# PGTN021_octasource_mkiii_controls.net
KiCad netlist of a schematic drawn in EAGLE
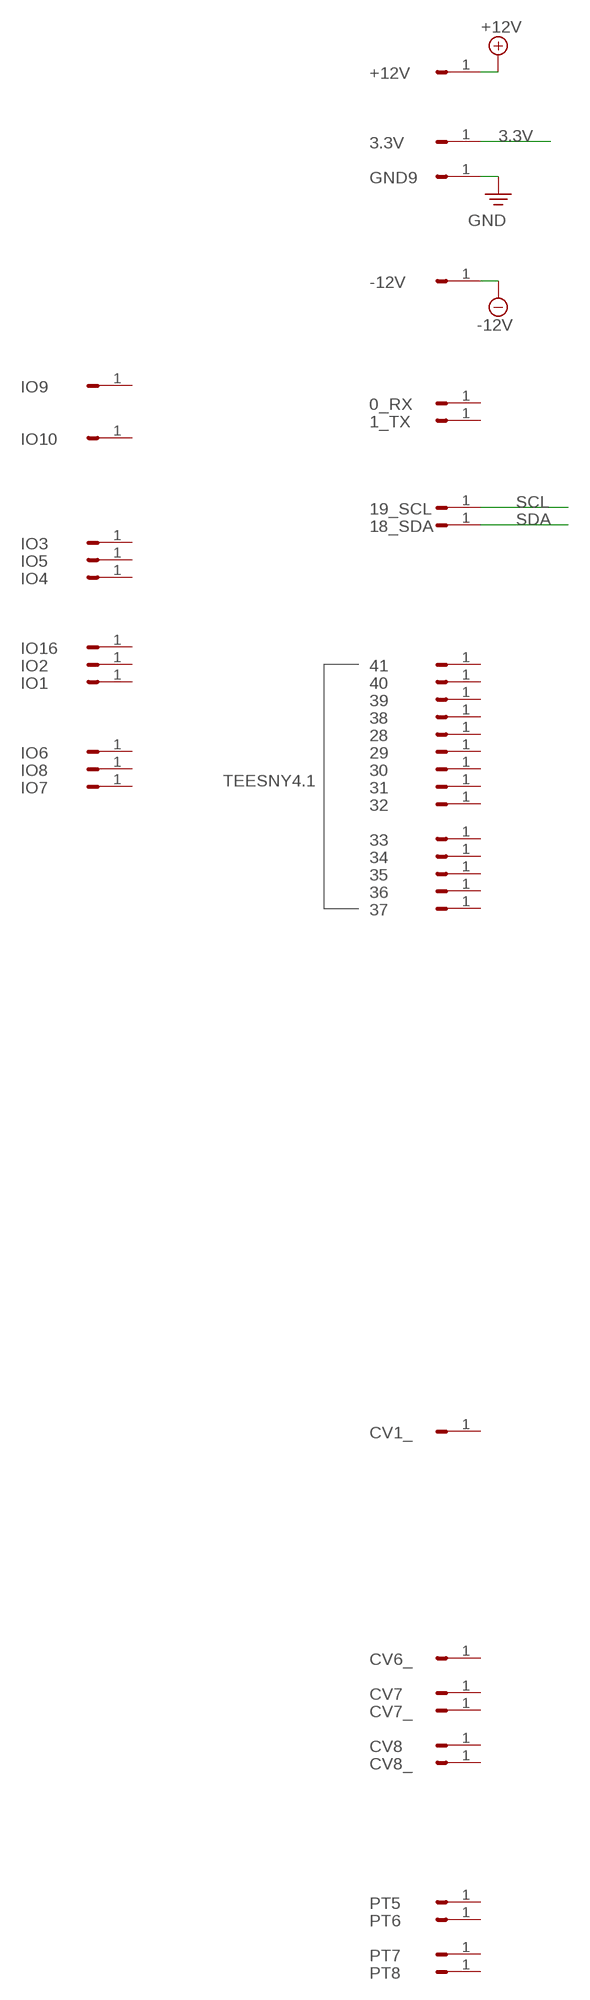
[diagram p0: schematic, sheet 1, part 1 of 2]
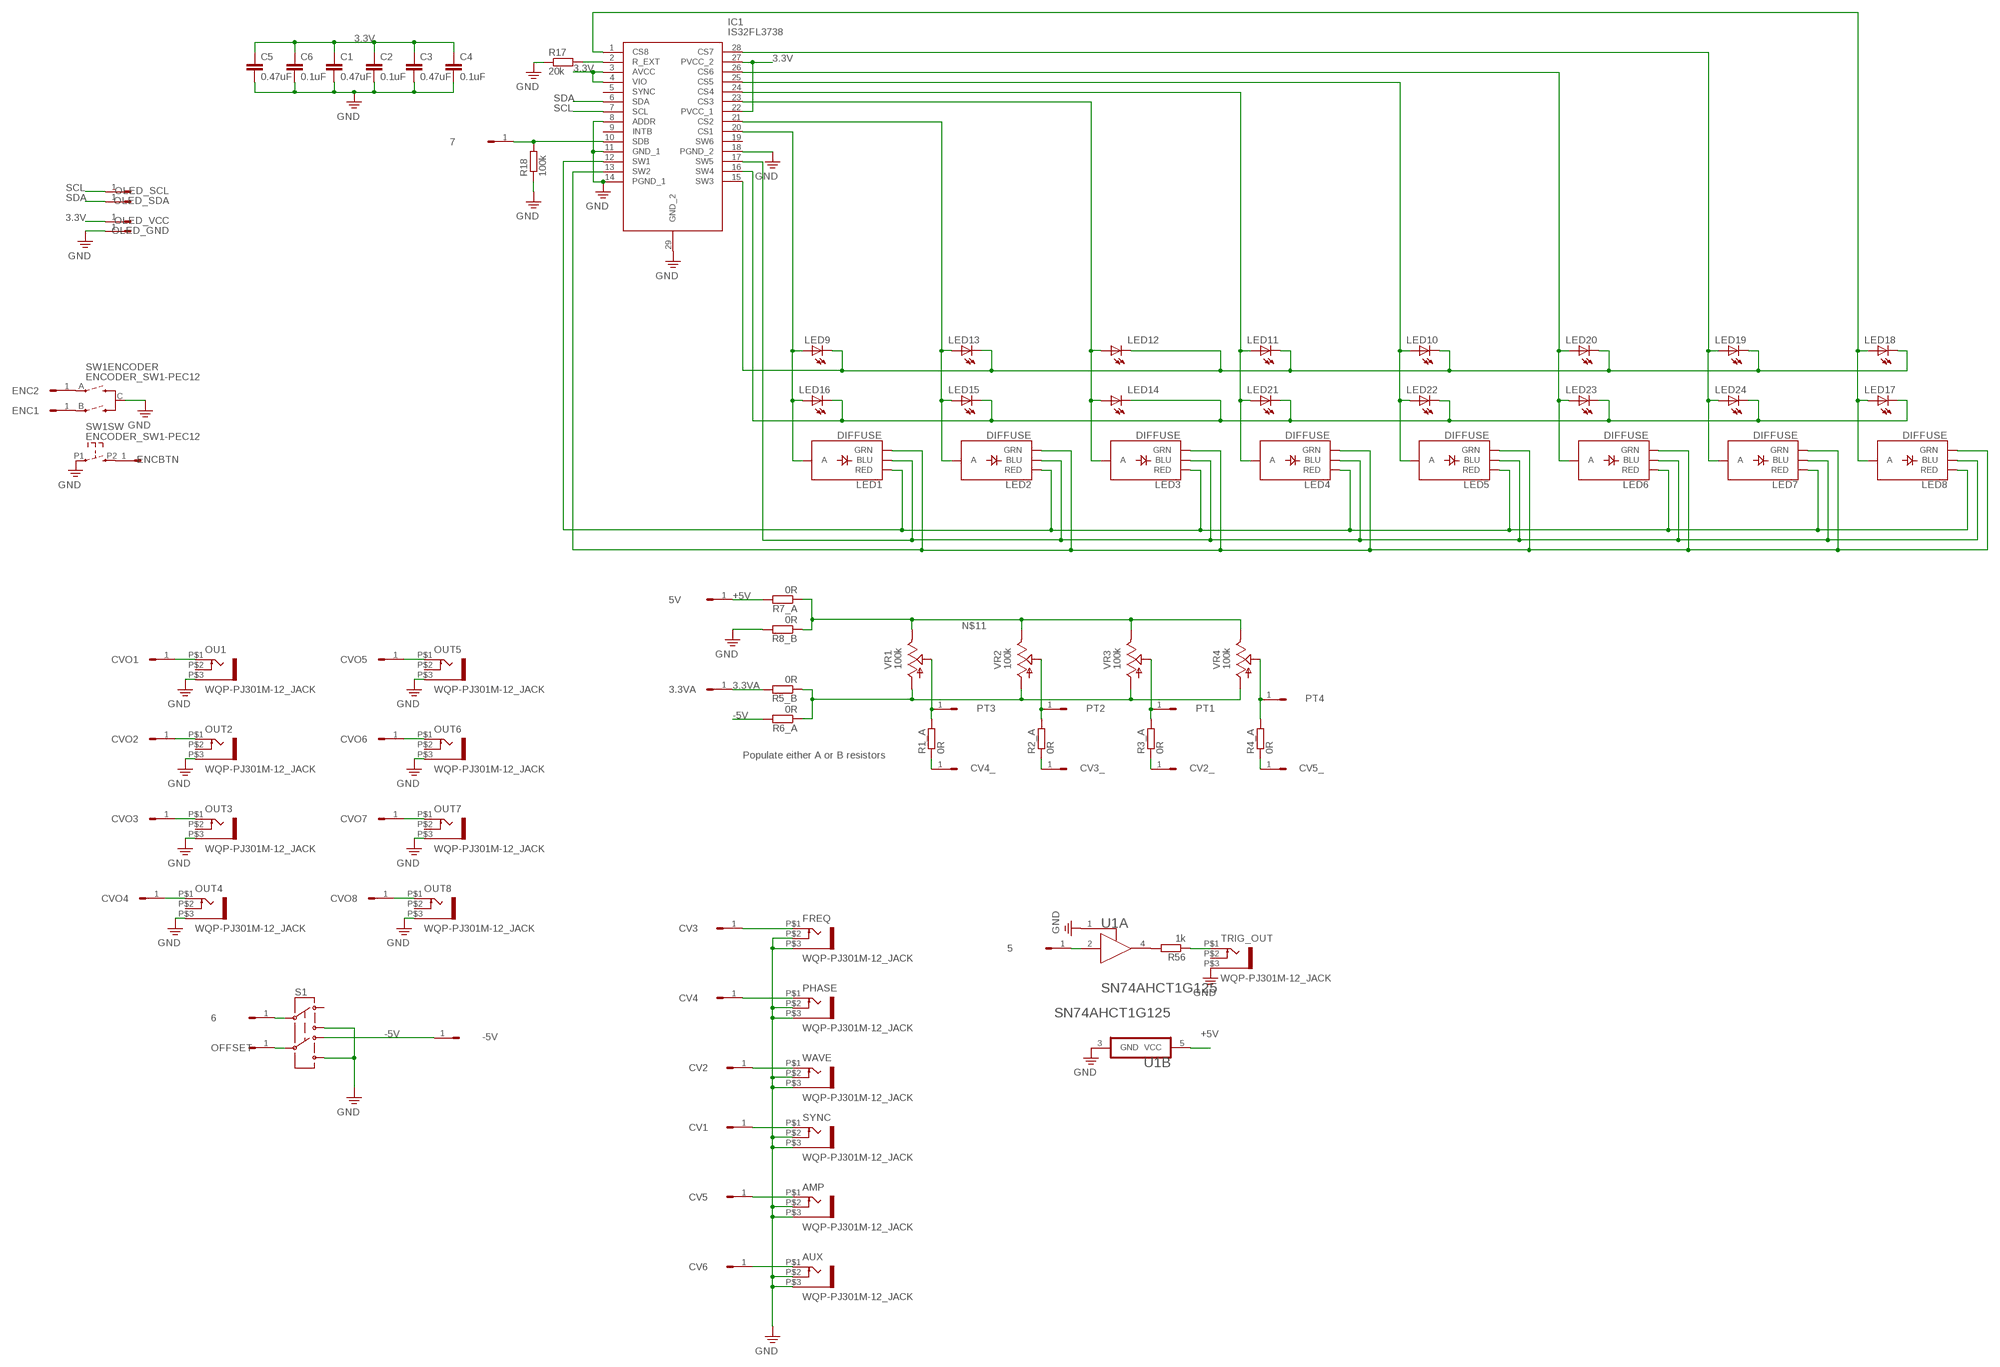
[diagram p1: schematic, sheet 1, part 2 of 2]

(export (version "E")
  (design (tool "Eeschema 10.0.6"))
  (components
    (comp (ref "+12V")
      (value "HEADER/MALE/01")
      (footprint "eagle-import:HEADER_MALE_01")
      (fields (field (name "SPICEPREFIX") "X"))
      (libsource (lib "eagle-import") (part "HEADER/MALE/01"))
    )
    (comp (ref "-5V")
      (value "HEADER/MALE/01")
      (footprint "eagle-import:HEADER_MALE_01")
      (fields (field (name "SPICEPREFIX") "X"))
      (libsource (lib "eagle-import") (part "HEADER/MALE/01"))
    )
    (comp (ref "-12V")
      (value "HEADER/MALE/01")
      (footprint "eagle-import:HEADER_MALE_01")
      (fields (field (name "SPICEPREFIX") "X"))
      (libsource (lib "eagle-import") (part "HEADER/MALE/01"))
    )
    (comp (ref "0_RX")
      (value "HEADER/MALE/01")
      (footprint "eagle-import:HEADER_MALE_01")
      (fields (field (name "SPICEPREFIX") "X"))
      (libsource (lib "eagle-import") (part "HEADER/MALE/01"))
    )
    (comp (ref "1_TX")
      (value "HEADER/MALE/01")
      (footprint "eagle-import:HEADER_MALE_01")
      (fields (field (name "SPICEPREFIX") "X"))
      (libsource (lib "eagle-import") (part "HEADER/MALE/01"))
    )
    (comp (ref "3.3V")
      (value "HEADER/MALE/01")
      (footprint "eagle-import:HEADER_MALE_01")
      (fields (field (name "SPICEPREFIX") "X"))
      (libsource (lib "eagle-import") (part "HEADER/MALE/01"))
    )
    (comp (ref "3.3VA")
      (value "HEADER/MALE/01")
      (footprint "eagle-import:HEADER_MALE_01")
      (fields (field (name "SPICEPREFIX") "X"))
      (libsource (lib "eagle-import") (part "HEADER/MALE/01"))
    )
    (comp (ref "5")
      (value "HEADER/MALE/01")
      (footprint "eagle-import:HEADER_MALE_01")
      (fields (field (name "SPICEPREFIX") "X"))
      (libsource (lib "eagle-import") (part "HEADER/MALE/01"))
    )
    (comp (ref "5V")
      (value "HEADER/MALE/01")
      (footprint "eagle-import:HEADER_MALE_01")
      (fields (field (name "SPICEPREFIX") "X"))
      (libsource (lib "eagle-import") (part "HEADER/MALE/01"))
    )
    (comp (ref "6")
      (value "HEADER/MALE/01")
      (footprint "eagle-import:HEADER_MALE_01")
      (fields (field (name "SPICEPREFIX") "X"))
      (libsource (lib "eagle-import") (part "HEADER/MALE/01"))
    )
    (comp (ref "7")
      (value "HEADER/MALE/01")
      (footprint "eagle-import:HEADER_MALE_01")
      (fields (field (name "SPICEPREFIX") "X"))
      (libsource (lib "eagle-import") (part "HEADER/MALE/01"))
    )
    (comp (ref "18_SDA")
      (value "HEADER/MALE/01")
      (footprint "eagle-import:HEADER_MALE_01")
      (fields (field (name "SPICEPREFIX") "X"))
      (libsource (lib "eagle-import") (part "HEADER/MALE/01"))
    )
    (comp (ref "19_SCL")
      (value "HEADER/MALE/01")
      (footprint "eagle-import:HEADER_MALE_01")
      (fields (field (name "SPICEPREFIX") "X"))
      (libsource (lib "eagle-import") (part "HEADER/MALE/01"))
    )
    (comp (ref "28")
      (value "HEADER/MALE/01")
      (footprint "eagle-import:HEADER_MALE_01")
      (fields (field (name "SPICEPREFIX") "X"))
      (libsource (lib "eagle-import") (part "HEADER/MALE/01"))
    )
    (comp (ref "29")
      (value "HEADER/MALE/01")
      (footprint "eagle-import:HEADER_MALE_01")
      (fields (field (name "SPICEPREFIX") "X"))
      (libsource (lib "eagle-import") (part "HEADER/MALE/01"))
    )
    (comp (ref "30")
      (value "HEADER/MALE/01")
      (footprint "eagle-import:HEADER_MALE_01")
      (fields (field (name "SPICEPREFIX") "X"))
      (libsource (lib "eagle-import") (part "HEADER/MALE/01"))
    )
    (comp (ref "31")
      (value "HEADER/MALE/01")
      (footprint "eagle-import:HEADER_MALE_01")
      (fields (field (name "SPICEPREFIX") "X"))
      (libsource (lib "eagle-import") (part "HEADER/MALE/01"))
    )
    (comp (ref "32")
      (value "HEADER/MALE/01")
      (footprint "eagle-import:HEADER_MALE_01")
      (fields (field (name "SPICEPREFIX") "X"))
      (libsource (lib "eagle-import") (part "HEADER/MALE/01"))
    )
    (comp (ref "33")
      (value "HEADER/MALE/01")
      (footprint "eagle-import:HEADER_MALE_01")
      (fields (field (name "SPICEPREFIX") "X"))
      (libsource (lib "eagle-import") (part "HEADER/MALE/01"))
    )
    (comp (ref "34")
      (value "HEADER/MALE/01")
      (footprint "eagle-import:HEADER_MALE_01")
      (fields (field (name "SPICEPREFIX") "X"))
      (libsource (lib "eagle-import") (part "HEADER/MALE/01"))
    )
    (comp (ref "35")
      (value "HEADER/MALE/01")
      (footprint "eagle-import:HEADER_MALE_01")
      (fields (field (name "SPICEPREFIX") "X"))
      (libsource (lib "eagle-import") (part "HEADER/MALE/01"))
    )
    (comp (ref "36")
      (value "HEADER/MALE/01")
      (footprint "eagle-import:HEADER_MALE_01")
      (fields (field (name "SPICEPREFIX") "X"))
      (libsource (lib "eagle-import") (part "HEADER/MALE/01"))
    )
    (comp (ref "37")
      (value "HEADER/MALE/01")
      (footprint "eagle-import:HEADER_MALE_01")
      (fields (field (name "SPICEPREFIX") "X"))
      (libsource (lib "eagle-import") (part "HEADER/MALE/01"))
    )
    (comp (ref "38")
      (value "HEADER/MALE/01")
      (footprint "eagle-import:HEADER_MALE_01")
      (fields (field (name "SPICEPREFIX") "X"))
      (libsource (lib "eagle-import") (part "HEADER/MALE/01"))
    )
    (comp (ref "39")
      (value "HEADER/MALE/01")
      (footprint "eagle-import:HEADER_MALE_01")
      (fields (field (name "SPICEPREFIX") "X"))
      (libsource (lib "eagle-import") (part "HEADER/MALE/01"))
    )
    (comp (ref "40")
      (value "HEADER/MALE/01")
      (footprint "eagle-import:HEADER_MALE_01")
      (fields (field (name "SPICEPREFIX") "X"))
      (libsource (lib "eagle-import") (part "HEADER/MALE/01"))
    )
    (comp (ref "41")
      (value "HEADER/MALE/01")
      (footprint "eagle-import:HEADER_MALE_01")
      (fields (field (name "SPICEPREFIX") "X"))
      (libsource (lib "eagle-import") (part "HEADER/MALE/01"))
    )
    (comp (ref "AMP")
      (value "WQP-PJ301M-12_JACK")
      (footprint "eagle-import:WQP-PJ301M-12_JACK")
      (libsource (lib "eagle-import") (part "WQP-PJ301M-12_JACK"))
    )
    (comp (ref "AUX")
      (value "WQP-PJ301M-12_JACK")
      (footprint "eagle-import:WQP-PJ301M-12_JACK")
      (libsource (lib "eagle-import") (part "WQP-PJ301M-12_JACK"))
    )
    (comp (ref "C1")
      (value "0.47uF")
      (footprint "eagle-import:C0603")
      (libsource (lib "eagle-import") (part "CAPACITORC0603"))
    )
    (comp (ref "C2")
      (value "0.1uF")
      (footprint "eagle-import:C0603")
      (libsource (lib "eagle-import") (part "CAPACITORC0603"))
    )
    (comp (ref "C3")
      (value "0.47uF")
      (footprint "eagle-import:C0603")
      (libsource (lib "eagle-import") (part "CAPACITORC0603"))
    )
    (comp (ref "C4")
      (value "0.1uF")
      (footprint "eagle-import:C0603")
      (libsource (lib "eagle-import") (part "CAPACITORC0603"))
    )
    (comp (ref "C5")
      (value "0.47uF")
      (footprint "eagle-import:C0603")
      (libsource (lib "eagle-import") (part "CAPACITORC0603"))
    )
    (comp (ref "C6")
      (value "0.1uF")
      (footprint "eagle-import:C0603")
      (libsource (lib "eagle-import") (part "CAPACITORC0603"))
    )
    (comp (ref "CV1")
      (value "HEADER/MALE/01")
      (footprint "eagle-import:HEADER_MALE_01")
      (fields (field (name "SPICEPREFIX") "X"))
      (libsource (lib "eagle-import") (part "HEADER/MALE/01"))
    )
    (comp (ref "CV1_")
      (value "HEADER/MALE/01")
      (footprint "eagle-import:HEADER_MALE_01")
      (fields (field (name "SPICEPREFIX") "X"))
      (libsource (lib "eagle-import") (part "HEADER/MALE/01"))
    )
    (comp (ref "CV2")
      (value "HEADER/MALE/01")
      (footprint "eagle-import:HEADER_MALE_01")
      (fields (field (name "SPICEPREFIX") "X"))
      (libsource (lib "eagle-import") (part "HEADER/MALE/01"))
    )
    (comp (ref "CV2_")
      (value "HEADER/MALE/01")
      (footprint "eagle-import:HEADER_MALE_01")
      (fields (field (name "SPICEPREFIX") "X"))
      (libsource (lib "eagle-import") (part "HEADER/MALE/01"))
    )
    (comp (ref "CV3")
      (value "HEADER/MALE/01")
      (footprint "eagle-import:HEADER_MALE_01")
      (fields (field (name "SPICEPREFIX") "X"))
      (libsource (lib "eagle-import") (part "HEADER/MALE/01"))
    )
    (comp (ref "CV3_")
      (value "HEADER/MALE/01")
      (footprint "eagle-import:HEADER_MALE_01")
      (fields (field (name "SPICEPREFIX") "X"))
      (libsource (lib "eagle-import") (part "HEADER/MALE/01"))
    )
    (comp (ref "CV4")
      (value "HEADER/MALE/01")
      (footprint "eagle-import:HEADER_MALE_01")
      (fields (field (name "SPICEPREFIX") "X"))
      (libsource (lib "eagle-import") (part "HEADER/MALE/01"))
    )
    (comp (ref "CV4_")
      (value "HEADER/MALE/01")
      (footprint "eagle-import:HEADER_MALE_01")
      (fields (field (name "SPICEPREFIX") "X"))
      (libsource (lib "eagle-import") (part "HEADER/MALE/01"))
    )
    (comp (ref "CV5")
      (value "HEADER/MALE/01")
      (footprint "eagle-import:HEADER_MALE_01")
      (fields (field (name "SPICEPREFIX") "X"))
      (libsource (lib "eagle-import") (part "HEADER/MALE/01"))
    )
    (comp (ref "CV5_")
      (value "HEADER/MALE/01")
      (footprint "eagle-import:HEADER_MALE_01")
      (fields (field (name "SPICEPREFIX") "X"))
      (libsource (lib "eagle-import") (part "HEADER/MALE/01"))
    )
    (comp (ref "CV6")
      (value "HEADER/MALE/01")
      (footprint "eagle-import:HEADER_MALE_01")
      (fields (field (name "SPICEPREFIX") "X"))
      (libsource (lib "eagle-import") (part "HEADER/MALE/01"))
    )
    (comp (ref "CV6_")
      (value "HEADER/MALE/01")
      (footprint "eagle-import:HEADER_MALE_01")
      (fields (field (name "SPICEPREFIX") "X"))
      (libsource (lib "eagle-import") (part "HEADER/MALE/01"))
    )
    (comp (ref "CV7")
      (value "HEADER/MALE/01")
      (footprint "eagle-import:HEADER_MALE_01")
      (fields (field (name "SPICEPREFIX") "X"))
      (libsource (lib "eagle-import") (part "HEADER/MALE/01"))
    )
    (comp (ref "CV7_")
      (value "HEADER/MALE/01")
      (footprint "eagle-import:HEADER_MALE_01")
      (fields (field (name "SPICEPREFIX") "X"))
      (libsource (lib "eagle-import") (part "HEADER/MALE/01"))
    )
    (comp (ref "CV8")
      (value "HEADER/MALE/01")
      (footprint "eagle-import:HEADER_MALE_01")
      (fields (field (name "SPICEPREFIX") "X"))
      (libsource (lib "eagle-import") (part "HEADER/MALE/01"))
    )
    (comp (ref "CV8_")
      (value "HEADER/MALE/01")
      (footprint "eagle-import:HEADER_MALE_01")
      (fields (field (name "SPICEPREFIX") "X"))
      (libsource (lib "eagle-import") (part "HEADER/MALE/01"))
    )
    (comp (ref "CVO1")
      (value "HEADER/MALE/01")
      (footprint "eagle-import:HEADER_MALE_01")
      (fields (field (name "SPICEPREFIX") "X"))
      (libsource (lib "eagle-import") (part "HEADER/MALE/01"))
    )
    (comp (ref "CVO2")
      (value "HEADER/MALE/01")
      (footprint "eagle-import:HEADER_MALE_01")
      (fields (field (name "SPICEPREFIX") "X"))
      (libsource (lib "eagle-import") (part "HEADER/MALE/01"))
    )
    (comp (ref "CVO3")
      (value "HEADER/MALE/01")
      (footprint "eagle-import:HEADER_MALE_01")
      (fields (field (name "SPICEPREFIX") "X"))
      (libsource (lib "eagle-import") (part "HEADER/MALE/01"))
    )
    (comp (ref "CVO4")
      (value "HEADER/MALE/01")
      (footprint "eagle-import:HEADER_MALE_01")
      (fields (field (name "SPICEPREFIX") "X"))
      (libsource (lib "eagle-import") (part "HEADER/MALE/01"))
    )
    (comp (ref "CVO5")
      (value "HEADER/MALE/01")
      (footprint "eagle-import:HEADER_MALE_01")
      (fields (field (name "SPICEPREFIX") "X"))
      (libsource (lib "eagle-import") (part "HEADER/MALE/01"))
    )
    (comp (ref "CVO6")
      (value "HEADER/MALE/01")
      (footprint "eagle-import:HEADER_MALE_01")
      (fields (field (name "SPICEPREFIX") "X"))
      (libsource (lib "eagle-import") (part "HEADER/MALE/01"))
    )
    (comp (ref "CVO7")
      (value "HEADER/MALE/01")
      (footprint "eagle-import:HEADER_MALE_01")
      (fields (field (name "SPICEPREFIX") "X"))
      (libsource (lib "eagle-import") (part "HEADER/MALE/01"))
    )
    (comp (ref "CVO8")
      (value "HEADER/MALE/01")
      (footprint "eagle-import:HEADER_MALE_01")
      (fields (field (name "SPICEPREFIX") "X"))
      (libsource (lib "eagle-import") (part "HEADER/MALE/01"))
    )
    (comp (ref "ENC1")
      (value "HEADER/MALE/01")
      (footprint "eagle-import:HEADER_MALE_01")
      (fields (field (name "SPICEPREFIX") "X"))
      (libsource (lib "eagle-import") (part "HEADER/MALE/01"))
    )
    (comp (ref "ENC2")
      (value "HEADER/MALE/01")
      (footprint "eagle-import:HEADER_MALE_01")
      (fields (field (name "SPICEPREFIX") "X"))
      (libsource (lib "eagle-import") (part "HEADER/MALE/01"))
    )
    (comp (ref "ENCBTN")
      (value "HEADER/MALE/01")
      (footprint "eagle-import:HEADER_MALE_01")
      (fields (field (name "SPICEPREFIX") "X"))
      (libsource (lib "eagle-import") (part "HEADER/MALE/01"))
    )
    (comp (ref "FREQ")
      (value "WQP-PJ301M-12_JACK")
      (footprint "eagle-import:WQP-PJ301M-12_JACK")
      (libsource (lib "eagle-import") (part "WQP-PJ301M-12_JACK"))
    )
    (comp (ref "GND9")
      (value "HEADER/MALE/01")
      (footprint "eagle-import:HEADER_MALE_01")
      (fields (field (name "SPICEPREFIX") "X"))
      (libsource (lib "eagle-import") (part "HEADER/MALE/01"))
    )
    (comp (ref "IC1")
      (value "IS32FL3738")
      (footprint "eagle-import:TSSOP29")
      (fields (field (name "MANUFACTURER_PART_NUMBER") "IS32FL3738-ZLA3-TR"))
      (libsource (lib "eagle-import") (part "IS32FL3738"))
    )
    (comp (ref "IO1")
      (value "HEADER/MALE/01")
      (footprint "eagle-import:HEADER_MALE_01")
      (fields (field (name "SPICEPREFIX") "X"))
      (libsource (lib "eagle-import") (part "HEADER/MALE/01"))
    )
    (comp (ref "IO2")
      (value "HEADER/MALE/01")
      (footprint "eagle-import:HEADER_MALE_01")
      (fields (field (name "SPICEPREFIX") "X"))
      (libsource (lib "eagle-import") (part "HEADER/MALE/01"))
    )
    (comp (ref "IO3")
      (value "HEADER/MALE/01")
      (footprint "eagle-import:HEADER_MALE_01")
      (fields (field (name "SPICEPREFIX") "X"))
      (libsource (lib "eagle-import") (part "HEADER/MALE/01"))
    )
    (comp (ref "IO4")
      (value "HEADER/MALE/01")
      (footprint "eagle-import:HEADER_MALE_01")
      (fields (field (name "SPICEPREFIX") "X"))
      (libsource (lib "eagle-import") (part "HEADER/MALE/01"))
    )
    (comp (ref "IO5")
      (value "HEADER/MALE/01")
      (footprint "eagle-import:HEADER_MALE_01")
      (fields (field (name "SPICEPREFIX") "X"))
      (libsource (lib "eagle-import") (part "HEADER/MALE/01"))
    )
    (comp (ref "IO6")
      (value "HEADER/MALE/01")
      (footprint "eagle-import:HEADER_MALE_01")
      (fields (field (name "SPICEPREFIX") "X"))
      (libsource (lib "eagle-import") (part "HEADER/MALE/01"))
    )
    (comp (ref "IO7")
      (value "HEADER/MALE/01")
      (footprint "eagle-import:HEADER_MALE_01")
      (fields (field (name "SPICEPREFIX") "X"))
      (libsource (lib "eagle-import") (part "HEADER/MALE/01"))
    )
    (comp (ref "IO8")
      (value "HEADER/MALE/01")
      (footprint "eagle-import:HEADER_MALE_01")
      (fields (field (name "SPICEPREFIX") "X"))
      (libsource (lib "eagle-import") (part "HEADER/MALE/01"))
    )
    (comp (ref "IO9")
      (value "HEADER/MALE/01")
      (footprint "eagle-import:HEADER_MALE_01")
      (fields (field (name "SPICEPREFIX") "X"))
      (libsource (lib "eagle-import") (part "HEADER/MALE/01"))
    )
    (comp (ref "IO10")
      (value "HEADER/MALE/01")
      (footprint "eagle-import:HEADER_MALE_01")
      (fields (field (name "SPICEPREFIX") "X"))
      (libsource (lib "eagle-import") (part "HEADER/MALE/01"))
    )
    (comp (ref "IO16")
      (value "HEADER/MALE/01")
      (footprint "eagle-import:HEADER_MALE_01")
      (fields (field (name "SPICEPREFIX") "X"))
      (libsource (lib "eagle-import") (part "HEADER/MALE/01"))
    )
    (comp (ref "LED1")
      (value "DIFFUSE")
      (footprint "eagle-import:LED-RGB-THRU")
      (libsource (lib "eagle-import") (part "LED-RGB-CADIFFUSE"))
    )
    (comp (ref "LED2")
      (value "DIFFUSE")
      (footprint "eagle-import:LED-RGB-THRU")
      (libsource (lib "eagle-import") (part "LED-RGB-CADIFFUSE"))
    )
    (comp (ref "LED3")
      (value "DIFFUSE")
      (footprint "eagle-import:LED-RGB-THRU")
      (libsource (lib "eagle-import") (part "LED-RGB-CADIFFUSE"))
    )
    (comp (ref "LED4")
      (value "DIFFUSE")
      (footprint "eagle-import:LED-RGB-THRU")
      (libsource (lib "eagle-import") (part "LED-RGB-CADIFFUSE"))
    )
    (comp (ref "LED5")
      (value "DIFFUSE")
      (footprint "eagle-import:LED-RGB-THRU")
      (libsource (lib "eagle-import") (part "LED-RGB-CADIFFUSE"))
    )
    (comp (ref "LED6")
      (value "DIFFUSE")
      (footprint "eagle-import:LED-RGB-THRU")
      (libsource (lib "eagle-import") (part "LED-RGB-CADIFFUSE"))
    )
    (comp (ref "LED7")
      (value "DIFFUSE")
      (footprint "eagle-import:LED-RGB-THRU")
      (libsource (lib "eagle-import") (part "LED-RGB-CADIFFUSE"))
    )
    (comp (ref "LED8")
      (value "DIFFUSE")
      (footprint "eagle-import:LED-RGB-THRU")
      (libsource (lib "eagle-import") (part "LED-RGB-CADIFFUSE"))
    )
    (comp (ref "LED9")
      (value "LEDCHIPLED_0805")
      (footprint "eagle-import:CHIPLED_0805")
      (libsource (lib "eagle-import") (part "LEDCHIPLED_0805"))
    )
    (comp (ref "LED10")
      (value "LEDCHIPLED_0805")
      (footprint "eagle-import:CHIPLED_0805")
      (libsource (lib "eagle-import") (part "LEDCHIPLED_0805"))
    )
    (comp (ref "LED11")
      (value "LEDCHIPLED_0805")
      (footprint "eagle-import:CHIPLED_0805")
      (libsource (lib "eagle-import") (part "LEDCHIPLED_0805"))
    )
    (comp (ref "LED12")
      (value "LEDCHIPLED_0805")
      (footprint "eagle-import:CHIPLED_0805")
      (libsource (lib "eagle-import") (part "LEDCHIPLED_0805"))
    )
    (comp (ref "LED13")
      (value "LEDCHIPLED_0805")
      (footprint "eagle-import:CHIPLED_0805")
      (libsource (lib "eagle-import") (part "LEDCHIPLED_0805"))
    )
    (comp (ref "LED14")
      (value "LEDCHIPLED_0805")
      (footprint "eagle-import:CHIPLED_0805")
      (libsource (lib "eagle-import") (part "LEDCHIPLED_0805"))
    )
    (comp (ref "LED15")
      (value "LEDCHIPLED_0805")
      (footprint "eagle-import:CHIPLED_0805")
      (libsource (lib "eagle-import") (part "LEDCHIPLED_0805"))
    )
    (comp (ref "LED16")
      (value "LEDCHIPLED_0805")
      (footprint "eagle-import:CHIPLED_0805")
      (libsource (lib "eagle-import") (part "LEDCHIPLED_0805"))
    )
    (comp (ref "LED17")
      (value "LEDCHIPLED_0805")
      (footprint "eagle-import:CHIPLED_0805")
      (libsource (lib "eagle-import") (part "LEDCHIPLED_0805"))
    )
    (comp (ref "LED18")
      (value "LEDCHIPLED_0805")
      (footprint "eagle-import:CHIPLED_0805")
      (libsource (lib "eagle-import") (part "LEDCHIPLED_0805"))
    )
    (comp (ref "LED19")
      (value "LEDCHIPLED_0805")
      (footprint "eagle-import:CHIPLED_0805")
      (libsource (lib "eagle-import") (part "LEDCHIPLED_0805"))
    )
    (comp (ref "LED20")
      (value "LEDCHIPLED_0805")
      (footprint "eagle-import:CHIPLED_0805")
      (libsource (lib "eagle-import") (part "LEDCHIPLED_0805"))
    )
    (comp (ref "LED21")
      (value "LEDCHIPLED_0805")
      (footprint "eagle-import:CHIPLED_0805")
      (libsource (lib "eagle-import") (part "LEDCHIPLED_0805"))
    )
    (comp (ref "LED22")
      (value "LEDCHIPLED_0805")
      (footprint "eagle-import:CHIPLED_0805")
      (libsource (lib "eagle-import") (part "LEDCHIPLED_0805"))
    )
    (comp (ref "LED23")
      (value "LEDCHIPLED_0805")
      (footprint "eagle-import:CHIPLED_0805")
      (libsource (lib "eagle-import") (part "LEDCHIPLED_0805"))
    )
    (comp (ref "LED24")
      (value "LEDCHIPLED_0805")
      (footprint "eagle-import:CHIPLED_0805")
      (libsource (lib "eagle-import") (part "LEDCHIPLED_0805"))
    )
    (comp (ref "OFFSET")
      (value "HEADER/MALE/01")
      (footprint "eagle-import:HEADER_MALE_01")
      (fields (field (name "SPICEPREFIX") "X"))
      (libsource (lib "eagle-import") (part "HEADER/MALE/01"))
    )
    (comp (ref "OLED_GND")
      (value "HEADER/MALE/01")
      (footprint "eagle-import:HEADER_MALE_01")
      (fields (field (name "SPICEPREFIX") "X"))
      (libsource (lib "eagle-import") (part "HEADER/MALE/01"))
    )
    (comp (ref "OLED_SCL")
      (value "HEADER/MALE/01")
      (footprint "eagle-import:HEADER_MALE_01")
      (fields (field (name "SPICEPREFIX") "X"))
      (libsource (lib "eagle-import") (part "HEADER/MALE/01"))
    )
    (comp (ref "OLED_SDA")
      (value "HEADER/MALE/01")
      (footprint "eagle-import:HEADER_MALE_01")
      (fields (field (name "SPICEPREFIX") "X"))
      (libsource (lib "eagle-import") (part "HEADER/MALE/01"))
    )
    (comp (ref "OLED_VCC")
      (value "HEADER/MALE/01")
      (footprint "eagle-import:HEADER_MALE_01")
      (fields (field (name "SPICEPREFIX") "X"))
      (libsource (lib "eagle-import") (part "HEADER/MALE/01"))
    )
    (comp (ref "OU1")
      (value "WQP-PJ301M-12_JACK")
      (footprint "eagle-import:WQP-PJ301M-12_JACK")
      (libsource (lib "eagle-import") (part "WQP-PJ301M-12_JACK"))
    )
    (comp (ref "OUT2")
      (value "WQP-PJ301M-12_JACK")
      (footprint "eagle-import:WQP-PJ301M-12_JACK")
      (libsource (lib "eagle-import") (part "WQP-PJ301M-12_JACK"))
    )
    (comp (ref "OUT3")
      (value "WQP-PJ301M-12_JACK")
      (footprint "eagle-import:WQP-PJ301M-12_JACK")
      (libsource (lib "eagle-import") (part "WQP-PJ301M-12_JACK"))
    )
    (comp (ref "OUT4")
      (value "WQP-PJ301M-12_JACK")
      (footprint "eagle-import:WQP-PJ301M-12_JACK")
      (libsource (lib "eagle-import") (part "WQP-PJ301M-12_JACK"))
    )
    (comp (ref "OUT5")
      (value "WQP-PJ301M-12_JACK")
      (footprint "eagle-import:WQP-PJ301M-12_JACK")
      (libsource (lib "eagle-import") (part "WQP-PJ301M-12_JACK"))
    )
    (comp (ref "OUT6")
      (value "WQP-PJ301M-12_JACK")
      (footprint "eagle-import:WQP-PJ301M-12_JACK")
      (libsource (lib "eagle-import") (part "WQP-PJ301M-12_JACK"))
    )
    (comp (ref "OUT7")
      (value "WQP-PJ301M-12_JACK")
      (footprint "eagle-import:WQP-PJ301M-12_JACK")
      (libsource (lib "eagle-import") (part "WQP-PJ301M-12_JACK"))
    )
    (comp (ref "OUT8")
      (value "WQP-PJ301M-12_JACK")
      (footprint "eagle-import:WQP-PJ301M-12_JACK")
      (libsource (lib "eagle-import") (part "WQP-PJ301M-12_JACK"))
    )
    (comp (ref "PHASE")
      (value "WQP-PJ301M-12_JACK")
      (footprint "eagle-import:WQP-PJ301M-12_JACK")
      (libsource (lib "eagle-import") (part "WQP-PJ301M-12_JACK"))
    )
    (comp (ref "PT1")
      (value "HEADER/MALE/01")
      (footprint "eagle-import:HEADER_MALE_01")
      (fields (field (name "SPICEPREFIX") "X"))
      (libsource (lib "eagle-import") (part "HEADER/MALE/01"))
    )
    (comp (ref "PT2")
      (value "HEADER/MALE/01")
      (footprint "eagle-import:HEADER_MALE_01")
      (fields (field (name "SPICEPREFIX") "X"))
      (libsource (lib "eagle-import") (part "HEADER/MALE/01"))
    )
    (comp (ref "PT3")
      (value "HEADER/MALE/01")
      (footprint "eagle-import:HEADER_MALE_01")
      (fields (field (name "SPICEPREFIX") "X"))
      (libsource (lib "eagle-import") (part "HEADER/MALE/01"))
    )
    (comp (ref "PT4")
      (value "HEADER/MALE/01")
      (footprint "eagle-import:HEADER_MALE_01")
      (fields (field (name "SPICEPREFIX") "X"))
      (libsource (lib "eagle-import") (part "HEADER/MALE/01"))
    )
    (comp (ref "PT5")
      (value "HEADER/MALE/01")
      (footprint "eagle-import:HEADER_MALE_01")
      (fields (field (name "SPICEPREFIX") "X"))
      (libsource (lib "eagle-import") (part "HEADER/MALE/01"))
    )
    (comp (ref "PT6")
      (value "HEADER/MALE/01")
      (footprint "eagle-import:HEADER_MALE_01")
      (fields (field (name "SPICEPREFIX") "X"))
      (libsource (lib "eagle-import") (part "HEADER/MALE/01"))
    )
    (comp (ref "PT7")
      (value "HEADER/MALE/01")
      (footprint "eagle-import:HEADER_MALE_01")
      (fields (field (name "SPICEPREFIX") "X"))
      (libsource (lib "eagle-import") (part "HEADER/MALE/01"))
    )
    (comp (ref "PT8")
      (value "HEADER/MALE/01")
      (footprint "eagle-import:HEADER_MALE_01")
      (fields (field (name "SPICEPREFIX") "X"))
      (libsource (lib "eagle-import") (part "HEADER/MALE/01"))
    )
    (comp (ref "R1_A")
      (value "0R")
      (footprint "eagle-import:R0603")
      (libsource (lib "eagle-import") (part "RESISTOR"))
    )
    (comp (ref "R2_A")
      (value "0R")
      (footprint "eagle-import:R0603")
      (libsource (lib "eagle-import") (part "RESISTOR"))
    )
    (comp (ref "R3_A")
      (value "0R")
      (footprint "eagle-import:R0603")
      (libsource (lib "eagle-import") (part "RESISTOR"))
    )
    (comp (ref "R4_A")
      (value "0R")
      (footprint "eagle-import:R0603")
      (libsource (lib "eagle-import") (part "RESISTOR"))
    )
    (comp (ref "R5_B")
      (value "0R")
      (footprint "eagle-import:R0603")
      (libsource (lib "eagle-import") (part "RESISTOR"))
    )
    (comp (ref "R6_A")
      (value "0R")
      (footprint "eagle-import:R0603")
      (libsource (lib "eagle-import") (part "RESISTOR"))
    )
    (comp (ref "R7_A")
      (value "0R")
      (footprint "eagle-import:R0603")
      (libsource (lib "eagle-import") (part "RESISTOR"))
    )
    (comp (ref "R8_B")
      (value "0R")
      (footprint "eagle-import:R0603")
      (libsource (lib "eagle-import") (part "RESISTOR"))
    )
    (comp (ref "R17")
      (value "20k")
      (footprint "eagle-import:R0603")
      (libsource (lib "eagle-import") (part "RESISTOR"))
    )
    (comp (ref "R18")
      (value "100k")
      (footprint "eagle-import:R0603")
      (libsource (lib "eagle-import") (part "RESISTOR"))
    )
    (comp (ref "R56")
      (value "1k")
      (footprint "eagle-import:R0603")
      (libsource (lib "eagle-import") (part "RESISTOR"))
    )
    (comp (ref "S1")
      (value "SWITCH-DPDTPTH2")
      (footprint "eagle-import:SWITCH-DPDT_SUB_ROUND")
      (libsource (lib "eagle-import") (part "SWITCH-DPDTPTH2"))
    )
    (comp (ref "SW1")
      (value "ENCODER_SW1-PEC12")
      (footprint "eagle-import:PEC12_INCREMENTAL_ENCODER")
      (libsource (lib "eagle-import") (part "ENCODER_SW1-PEC12"))
    )
    (comp (ref "SYNC")
      (value "WQP-PJ301M-12_JACK")
      (footprint "eagle-import:WQP-PJ301M-12_JACK")
      (libsource (lib "eagle-import") (part "WQP-PJ301M-12_JACK"))
    )
    (comp (ref "TRIG_OUT")
      (value "WQP-PJ301M-12_JACK")
      (footprint "eagle-import:WQP-PJ301M-12_JACK")
      (libsource (lib "eagle-import") (part "WQP-PJ301M-12_JACK"))
    )
    (comp (ref "U1")
      (value "74AHCT1G125")
      (footprint "eagle-import:74AHCT1G125")
      (fields (field (name "MF") "Texas Instruments") (field (name "MPN") "SN74AHCT1G125"))
      (libsource (lib "eagle-import") (part "74AHCT1G125{dblquote}"))
    )
    (comp (ref "VR1")
      (value "100k")
      (footprint "eagle-import:9MM_SNAP-IN_POT")
      (libsource (lib "eagle-import") (part "9MM_SNAP-IN_POT_"))
    )
    (comp (ref "VR2")
      (value "100k")
      (footprint "eagle-import:9MM_SNAP-IN_POT")
      (libsource (lib "eagle-import") (part "9MM_SNAP-IN_POT_"))
    )
    (comp (ref "VR3")
      (value "100k")
      (footprint "eagle-import:9MM_SNAP-IN_POT")
      (libsource (lib "eagle-import") (part "9MM_SNAP-IN_POT_"))
    )
    (comp (ref "VR4")
      (value "100k")
      (footprint "eagle-import:9MM_SNAP-IN_POT")
      (libsource (lib "eagle-import") (part "9MM_SNAP-IN_POT_"))
    )
    (comp (ref "WAVE")
      (value "WQP-PJ301M-12_JACK")
      (footprint "eagle-import:WQP-PJ301M-12_JACK")
      (libsource (lib "eagle-import") (part "WQP-PJ301M-12_JACK"))
    )
  )
  (nets
    (net (code "1") (name "+12V") (class "Default")
      (node (ref "+12V") (pin "1") (pinfunction "3_1") (pintype "passive"))
    )
    (net (code "2") (name "-12V") (class "Default")
      (node (ref "-12V") (pin "1") (pinfunction "3_1") (pintype "passive"))
    )
    (net (code "3") (name "/+5V") (class "Default")
      (node (ref "5V") (pin "1") (pinfunction "3_1") (pintype "passive"))
      (node (ref "R7_A") (pin "2") (pinfunction "2_2") (pintype "passive"))
      (node (ref "U1") (pin "5") (pinfunction "VCC_5") (pintype "power_in"))
    )
    (net (code "4") (name "/-5V") (class "Default")
      (node (ref "-5V") (pin "1") (pinfunction "3_1") (pintype "passive"))
      (node (ref "R6_A") (pin "2") (pinfunction "2_2") (pintype "passive"))
      (node (ref "S1") (pin "4") (pinfunction "4_4") (pintype "bidirectional"))
    )
    (net (code "5") (name "/3.3V") (class "Default")
      (node (ref "3.3V") (pin "1") (pinfunction "3_1") (pintype "passive"))
      (node (ref "C1") (pin "1") (pinfunction "1_1") (pintype "passive"))
      (node (ref "C2") (pin "1") (pinfunction "1_1") (pintype "passive"))
      (node (ref "C3") (pin "1") (pinfunction "1_1") (pintype "passive"))
      (node (ref "C4") (pin "1") (pinfunction "1_1") (pintype "passive"))
      (node (ref "C5") (pin "1") (pinfunction "1_1") (pintype "passive"))
      (node (ref "C6") (pin "1") (pinfunction "1_1") (pintype "passive"))
      (node (ref "IC1") (pin "22") (pinfunction "PVCC_1_22") (pintype "power_in"))
      (node (ref "IC1") (pin "27") (pinfunction "PVCC_2_27") (pintype "power_in"))
      (node (ref "IC1") (pin "3") (pinfunction "AVCC_3") (pintype "power_in"))
      (node (ref "IC1") (pin "4") (pinfunction "VIO_4") (pintype "input"))
      (node (ref "OLED_VCC") (pin "1") (pinfunction "3_1") (pintype "passive"))
    )
    (net (code "6") (name "/3.3VA") (class "Default")
      (node (ref "3.3VA") (pin "1") (pinfunction "3_1") (pintype "passive"))
      (node (ref "R5_B") (pin "2") (pinfunction "2_2") (pintype "passive"))
    )
    (net (code "7") (name "/N$11") (class "Default")
      (node (ref "R7_A") (pin "1") (pinfunction "1_1") (pintype "passive"))
      (node (ref "R8_B") (pin "1") (pinfunction "1_1") (pintype "passive"))
      (node (ref "VR1") (pin "3") (pinfunction "E_3") (pintype "passive"))
      (node (ref "VR2") (pin "3") (pinfunction "E_3") (pintype "passive"))
      (node (ref "VR3") (pin "3") (pinfunction "E_3") (pintype "passive"))
      (node (ref "VR4") (pin "3") (pinfunction "E_3") (pintype "passive"))
    )
    (net (code "8") (name "/SCL") (class "Default")
      (node (ref "19_SCL") (pin "1") (pinfunction "3_1") (pintype "passive"))
      (node (ref "IC1") (pin "7") (pinfunction "SCL_7") (pintype "bidirectional"))
      (node (ref "OLED_SCL") (pin "1") (pinfunction "3_1") (pintype "passive"))
    )
    (net (code "9") (name "/SDA") (class "Default")
      (node (ref "18_SDA") (pin "1") (pinfunction "3_1") (pintype "passive"))
      (node (ref "IC1") (pin "6") (pinfunction "SDA_6") (pintype "bidirectional"))
      (node (ref "OLED_SDA") (pin "1") (pinfunction "3_1") (pintype "passive"))
    )
    (net (code "10") (name "GND") (class "Default")
      (node (ref "AMP") (pin "P$2") (pinfunction "3_P$2") (pintype "passive"))
      (node (ref "AMP") (pin "P$3") (pinfunction "1_P$3") (pintype "passive"))
      (node (ref "AUX") (pin "P$2") (pinfunction "3_P$2") (pintype "passive"))
      (node (ref "AUX") (pin "P$3") (pinfunction "1_P$3") (pintype "passive"))
      (node (ref "C1") (pin "2") (pinfunction "2_2") (pintype "passive"))
      (node (ref "C2") (pin "2") (pinfunction "2_2") (pintype "passive"))
      (node (ref "C3") (pin "2") (pinfunction "2_2") (pintype "passive"))
      (node (ref "C4") (pin "2") (pinfunction "2_2") (pintype "passive"))
      (node (ref "C5") (pin "2") (pinfunction "2_2") (pintype "passive"))
      (node (ref "C6") (pin "2") (pinfunction "2_2") (pintype "passive"))
      (node (ref "FREQ") (pin "P$2") (pinfunction "3_P$2") (pintype "passive"))
      (node (ref "FREQ") (pin "P$3") (pinfunction "1_P$3") (pintype "passive"))
      (node (ref "GND9") (pin "1") (pinfunction "3_1") (pintype "passive"))
      (node (ref "IC1") (pin "11") (pinfunction "GND_1_11") (pintype "power_in"))
      (node (ref "IC1") (pin "14") (pinfunction "PGND_1_14") (pintype "power_in"))
      (node (ref "IC1") (pin "18") (pinfunction "PGND_2_18") (pintype "power_in"))
      (node (ref "IC1") (pin "29") (pinfunction "GND_2_29") (pintype "power_in"))
      (node (ref "IC1") (pin "8") (pinfunction "ADDR_8") (pintype "input"))
      (node (ref "OLED_GND") (pin "1") (pinfunction "3_1") (pintype "passive"))
      (node (ref "OU1") (pin "P$3") (pinfunction "1_P$3") (pintype "passive"))
      (node (ref "OUT2") (pin "P$3") (pinfunction "1_P$3") (pintype "passive"))
      (node (ref "OUT3") (pin "P$3") (pinfunction "1_P$3") (pintype "passive"))
      (node (ref "OUT4") (pin "P$3") (pinfunction "1_P$3") (pintype "passive"))
      (node (ref "OUT5") (pin "P$3") (pinfunction "1_P$3") (pintype "passive"))
      (node (ref "OUT6") (pin "P$3") (pinfunction "1_P$3") (pintype "passive"))
      (node (ref "OUT7") (pin "P$3") (pinfunction "1_P$3") (pintype "passive"))
      (node (ref "OUT8") (pin "P$3") (pinfunction "1_P$3") (pintype "passive"))
      (node (ref "PHASE") (pin "P$2") (pinfunction "3_P$2") (pintype "passive"))
      (node (ref "PHASE") (pin "P$3") (pinfunction "1_P$3") (pintype "passive"))
      (node (ref "R17") (pin "1") (pinfunction "1_1") (pintype "passive"))
      (node (ref "R18") (pin "1") (pinfunction "1_1") (pintype "passive"))
      (node (ref "R8_B") (pin "2") (pinfunction "2_2") (pintype "passive"))
      (node (ref "S1") (pin "3") (pinfunction "3_3") (pintype "bidirectional"))
      (node (ref "S1") (pin "6") (pinfunction "6_6") (pintype "bidirectional"))
      (node (ref "SW1") (pin "C") (pinfunction "C_C") (pintype "passive"))
      (node (ref "SW1") (pin "P1") (pinfunction "1_P1") (pintype "passive"))
      (node (ref "SYNC") (pin "P$2") (pinfunction "3_P$2") (pintype "passive"))
      (node (ref "SYNC") (pin "P$3") (pinfunction "1_P$3") (pintype "passive"))
      (node (ref "TRIG_OUT") (pin "P$3") (pinfunction "1_P$3") (pintype "passive"))
      (node (ref "U1") (pin "1") (pinfunction "~{OE}_1") (pintype "input"))
      (node (ref "U1") (pin "3") (pinfunction "GND_3") (pintype "power_in"))
      (node (ref "WAVE") (pin "P$2") (pinfunction "3_P$2") (pintype "passive"))
      (node (ref "WAVE") (pin "P$3") (pinfunction "1_P$3") (pintype "passive"))
    )
    (net (code "11") (name "Net-(5-3)") (class "Default")
      (node (ref "5") (pin "1") (pinfunction "3_1") (pintype "passive"))
      (node (ref "U1") (pin "2") (pinfunction "A_2") (pintype "input"))
    )
    (net (code "12") (name "Net-(6-3)") (class "Default")
      (node (ref "6") (pin "1") (pinfunction "3_1") (pintype "passive"))
      (node (ref "S1") (pin "2") (pinfunction "2_2") (pintype "bidirectional"))
    )
    (net (code "13") (name "Net-(7-3)") (class "Default")
      (node (ref "7") (pin "1") (pinfunction "3_1") (pintype "passive"))
      (node (ref "IC1") (pin "10") (pinfunction "SDB_10") (pintype "input"))
      (node (ref "R18") (pin "2") (pinfunction "2_2") (pintype "passive"))
    )
    (net (code "14") (name "Net-(AMP-2)") (class "Default")
      (node (ref "AMP") (pin "P$1") (pinfunction "2_P$1") (pintype "passive"))
      (node (ref "CV5") (pin "1") (pinfunction "3_1") (pintype "passive"))
    )
    (net (code "15") (name "Net-(AUX-2)") (class "Default")
      (node (ref "AUX") (pin "P$1") (pinfunction "2_P$1") (pintype "passive"))
      (node (ref "CV6") (pin "1") (pinfunction "3_1") (pintype "passive"))
    )
    (net (code "16") (name "Net-(CV1-3)") (class "Default")
      (node (ref "CV1") (pin "1") (pinfunction "3_1") (pintype "passive"))
      (node (ref "SYNC") (pin "P$1") (pinfunction "2_P$1") (pintype "passive"))
    )
    (net (code "17") (name "Net-(CV2-3)") (class "Default")
      (node (ref "CV2") (pin "1") (pinfunction "3_1") (pintype "passive"))
      (node (ref "WAVE") (pin "P$1") (pinfunction "2_P$1") (pintype "passive"))
    )
    (net (code "18") (name "Net-(CV2_-3)") (class "Default")
      (node (ref "CV2_") (pin "1") (pinfunction "3_1") (pintype "passive"))
      (node (ref "R3_A") (pin "1") (pinfunction "1_1") (pintype "passive"))
    )
    (net (code "19") (name "Net-(CV3-3)") (class "Default")
      (node (ref "CV3") (pin "1") (pinfunction "3_1") (pintype "passive"))
      (node (ref "FREQ") (pin "P$1") (pinfunction "2_P$1") (pintype "passive"))
    )
    (net (code "20") (name "Net-(CV3_-3)") (class "Default")
      (node (ref "CV3_") (pin "1") (pinfunction "3_1") (pintype "passive"))
      (node (ref "R2_A") (pin "1") (pinfunction "1_1") (pintype "passive"))
    )
    (net (code "21") (name "Net-(CV4-3)") (class "Default")
      (node (ref "CV4") (pin "1") (pinfunction "3_1") (pintype "passive"))
      (node (ref "PHASE") (pin "P$1") (pinfunction "2_P$1") (pintype "passive"))
    )
    (net (code "22") (name "Net-(CV4_-3)") (class "Default")
      (node (ref "CV4_") (pin "1") (pinfunction "3_1") (pintype "passive"))
      (node (ref "R1_A") (pin "1") (pinfunction "1_1") (pintype "passive"))
    )
    (net (code "23") (name "Net-(CV5_-3)") (class "Default")
      (node (ref "CV5_") (pin "1") (pinfunction "3_1") (pintype "passive"))
      (node (ref "R4_A") (pin "1") (pinfunction "1_1") (pintype "passive"))
    )
    (net (code "24") (name "Net-(CVO1-3)") (class "Default")
      (node (ref "CVO1") (pin "1") (pinfunction "3_1") (pintype "passive"))
      (node (ref "OU1") (pin "P$1") (pinfunction "2_P$1") (pintype "passive"))
    )
    (net (code "25") (name "Net-(CVO2-3)") (class "Default")
      (node (ref "CVO2") (pin "1") (pinfunction "3_1") (pintype "passive"))
      (node (ref "OUT2") (pin "P$1") (pinfunction "2_P$1") (pintype "passive"))
    )
    (net (code "26") (name "Net-(CVO3-3)") (class "Default")
      (node (ref "CVO3") (pin "1") (pinfunction "3_1") (pintype "passive"))
      (node (ref "OUT3") (pin "P$1") (pinfunction "2_P$1") (pintype "passive"))
    )
    (net (code "27") (name "Net-(CVO4-3)") (class "Default")
      (node (ref "CVO4") (pin "1") (pinfunction "3_1") (pintype "passive"))
      (node (ref "OUT4") (pin "P$1") (pinfunction "2_P$1") (pintype "passive"))
    )
    (net (code "28") (name "Net-(CVO5-3)") (class "Default")
      (node (ref "CVO5") (pin "1") (pinfunction "3_1") (pintype "passive"))
      (node (ref "OUT5") (pin "P$1") (pinfunction "2_P$1") (pintype "passive"))
    )
    (net (code "29") (name "Net-(CVO6-3)") (class "Default")
      (node (ref "CVO6") (pin "1") (pinfunction "3_1") (pintype "passive"))
      (node (ref "OUT6") (pin "P$1") (pinfunction "2_P$1") (pintype "passive"))
    )
    (net (code "30") (name "Net-(CVO7-3)") (class "Default")
      (node (ref "CVO7") (pin "1") (pinfunction "3_1") (pintype "passive"))
      (node (ref "OUT7") (pin "P$1") (pinfunction "2_P$1") (pintype "passive"))
    )
    (net (code "31") (name "Net-(CVO8-3)") (class "Default")
      (node (ref "CVO8") (pin "1") (pinfunction "3_1") (pintype "passive"))
      (node (ref "OUT8") (pin "P$1") (pinfunction "2_P$1") (pintype "passive"))
    )
    (net (code "32") (name "Net-(ENC1-3)") (class "Default")
      (node (ref "ENC1") (pin "1") (pinfunction "3_1") (pintype "passive"))
      (node (ref "SW1") (pin "B") (pinfunction "B_B") (pintype "passive"))
    )
    (net (code "33") (name "Net-(ENC2-3)") (class "Default")
      (node (ref "ENC2") (pin "1") (pinfunction "3_1") (pintype "passive"))
      (node (ref "SW1") (pin "A") (pinfunction "A_A") (pintype "passive"))
    )
    (net (code "34") (name "Net-(ENCBTN-3)") (class "Default")
      (node (ref "ENCBTN") (pin "1") (pinfunction "3_1") (pintype "passive"))
      (node (ref "SW1") (pin "P2") (pinfunction "2_P2") (pintype "passive"))
    )
    (net (code "35") (name "Net-(IC1-CS1)") (class "Default")
      (node (ref "IC1") (pin "20") (pinfunction "CS1_20") (pintype "output"))
      (node (ref "LED1") (pin "2") (pinfunction "A_2") (pintype "bidirectional"))
      (node (ref "LED16") (pin "A") (pinfunction "A_A") (pintype "passive"))
      (node (ref "LED9") (pin "A") (pinfunction "A_A") (pintype "passive"))
    )
    (net (code "36") (name "Net-(IC1-CS2)") (class "Default")
      (node (ref "IC1") (pin "21") (pinfunction "CS2_21") (pintype "output"))
      (node (ref "LED13") (pin "A") (pinfunction "A_A") (pintype "passive"))
      (node (ref "LED15") (pin "A") (pinfunction "A_A") (pintype "passive"))
      (node (ref "LED2") (pin "2") (pinfunction "A_2") (pintype "bidirectional"))
    )
    (net (code "37") (name "Net-(IC1-CS3)") (class "Default")
      (node (ref "IC1") (pin "23") (pinfunction "CS3_23") (pintype "bidirectional"))
      (node (ref "LED12") (pin "A") (pinfunction "A_A") (pintype "passive"))
      (node (ref "LED14") (pin "A") (pinfunction "A_A") (pintype "passive"))
      (node (ref "LED3") (pin "2") (pinfunction "A_2") (pintype "bidirectional"))
    )
    (net (code "38") (name "Net-(IC1-CS4)") (class "Default")
      (node (ref "IC1") (pin "24") (pinfunction "CS4_24") (pintype "bidirectional"))
      (node (ref "LED11") (pin "A") (pinfunction "A_A") (pintype "passive"))
      (node (ref "LED21") (pin "A") (pinfunction "A_A") (pintype "passive"))
      (node (ref "LED4") (pin "2") (pinfunction "A_2") (pintype "bidirectional"))
    )
    (net (code "39") (name "Net-(IC1-CS5)") (class "Default")
      (node (ref "IC1") (pin "25") (pinfunction "CS5_25") (pintype "bidirectional"))
      (node (ref "LED10") (pin "A") (pinfunction "A_A") (pintype "passive"))
      (node (ref "LED22") (pin "A") (pinfunction "A_A") (pintype "passive"))
      (node (ref "LED5") (pin "2") (pinfunction "A_2") (pintype "bidirectional"))
    )
    (net (code "40") (name "Net-(IC1-CS6)") (class "Default")
      (node (ref "IC1") (pin "26") (pinfunction "CS6_26") (pintype "bidirectional"))
      (node (ref "LED20") (pin "A") (pinfunction "A_A") (pintype "passive"))
      (node (ref "LED23") (pin "A") (pinfunction "A_A") (pintype "passive"))
      (node (ref "LED6") (pin "2") (pinfunction "A_2") (pintype "bidirectional"))
    )
    (net (code "41") (name "Net-(IC1-CS7)") (class "Default")
      (node (ref "IC1") (pin "28") (pinfunction "CS7_28") (pintype "output"))
      (node (ref "LED19") (pin "A") (pinfunction "A_A") (pintype "passive"))
      (node (ref "LED24") (pin "A") (pinfunction "A_A") (pintype "passive"))
      (node (ref "LED7") (pin "2") (pinfunction "A_2") (pintype "bidirectional"))
    )
    (net (code "42") (name "Net-(IC1-CS8)") (class "Default")
      (node (ref "IC1") (pin "1") (pinfunction "CS8_1") (pintype "output"))
      (node (ref "LED17") (pin "A") (pinfunction "A_A") (pintype "passive"))
      (node (ref "LED18") (pin "A") (pinfunction "A_A") (pintype "passive"))
      (node (ref "LED8") (pin "2") (pinfunction "A_2") (pintype "bidirectional"))
    )
    (net (code "43") (name "Net-(IC1-R_EXT)") (class "Default")
      (node (ref "IC1") (pin "2") (pinfunction "R_EXT_2") (pintype "input"))
      (node (ref "R17") (pin "2") (pinfunction "2_2") (pintype "passive"))
    )
    (net (code "44") (name "Net-(IC1-SW1)") (class "Default")
      (node (ref "IC1") (pin "12") (pinfunction "SW1_12") (pintype "output"))
      (node (ref "LED1") (pin "1") (pinfunction "RED_1") (pintype "bidirectional"))
      (node (ref "LED2") (pin "1") (pinfunction "RED_1") (pintype "bidirectional"))
      (node (ref "LED3") (pin "1") (pinfunction "RED_1") (pintype "bidirectional"))
      (node (ref "LED4") (pin "1") (pinfunction "RED_1") (pintype "bidirectional"))
      (node (ref "LED5") (pin "1") (pinfunction "RED_1") (pintype "bidirectional"))
      (node (ref "LED6") (pin "1") (pinfunction "RED_1") (pintype "bidirectional"))
      (node (ref "LED7") (pin "1") (pinfunction "RED_1") (pintype "bidirectional"))
      (node (ref "LED8") (pin "1") (pinfunction "RED_1") (pintype "bidirectional"))
    )
    (net (code "45") (name "Net-(IC1-SW2)") (class "Default")
      (node (ref "IC1") (pin "13") (pinfunction "SW2_13") (pintype "output"))
      (node (ref "LED1") (pin "3") (pinfunction "GRN_3") (pintype "bidirectional"))
      (node (ref "LED2") (pin "3") (pinfunction "GRN_3") (pintype "bidirectional"))
      (node (ref "LED3") (pin "3") (pinfunction "GRN_3") (pintype "bidirectional"))
      (node (ref "LED4") (pin "3") (pinfunction "GRN_3") (pintype "bidirectional"))
      (node (ref "LED5") (pin "3") (pinfunction "GRN_3") (pintype "bidirectional"))
      (node (ref "LED6") (pin "3") (pinfunction "GRN_3") (pintype "bidirectional"))
      (node (ref "LED7") (pin "3") (pinfunction "GRN_3") (pintype "bidirectional"))
      (node (ref "LED8") (pin "3") (pinfunction "GRN_3") (pintype "bidirectional"))
    )
    (net (code "46") (name "Net-(IC1-SW3)") (class "Default")
      (node (ref "IC1") (pin "15") (pinfunction "SW3_15") (pintype "output"))
      (node (ref "LED10") (pin "C") (pinfunction "C_C") (pintype "passive"))
      (node (ref "LED11") (pin "C") (pinfunction "C_C") (pintype "passive"))
      (node (ref "LED12") (pin "C") (pinfunction "C_C") (pintype "passive"))
      (node (ref "LED13") (pin "C") (pinfunction "C_C") (pintype "passive"))
      (node (ref "LED18") (pin "C") (pinfunction "C_C") (pintype "passive"))
      (node (ref "LED19") (pin "C") (pinfunction "C_C") (pintype "passive"))
      (node (ref "LED20") (pin "C") (pinfunction "C_C") (pintype "passive"))
      (node (ref "LED9") (pin "C") (pinfunction "C_C") (pintype "passive"))
    )
    (net (code "47") (name "Net-(IC1-SW4)") (class "Default")
      (node (ref "IC1") (pin "16") (pinfunction "SW4_16") (pintype "output"))
      (node (ref "LED14") (pin "C") (pinfunction "C_C") (pintype "passive"))
      (node (ref "LED15") (pin "C") (pinfunction "C_C") (pintype "passive"))
      (node (ref "LED16") (pin "C") (pinfunction "C_C") (pintype "passive"))
      (node (ref "LED17") (pin "C") (pinfunction "C_C") (pintype "passive"))
      (node (ref "LED21") (pin "C") (pinfunction "C_C") (pintype "passive"))
      (node (ref "LED22") (pin "C") (pinfunction "C_C") (pintype "passive"))
      (node (ref "LED23") (pin "C") (pinfunction "C_C") (pintype "passive"))
      (node (ref "LED24") (pin "C") (pinfunction "C_C") (pintype "passive"))
    )
    (net (code "48") (name "Net-(IC1-SW5)") (class "Default")
      (node (ref "IC1") (pin "17") (pinfunction "SW5_17") (pintype "output"))
      (node (ref "LED1") (pin "4") (pinfunction "BLU_4") (pintype "bidirectional"))
      (node (ref "LED2") (pin "4") (pinfunction "BLU_4") (pintype "bidirectional"))
      (node (ref "LED3") (pin "4") (pinfunction "BLU_4") (pintype "bidirectional"))
      (node (ref "LED4") (pin "4") (pinfunction "BLU_4") (pintype "bidirectional"))
      (node (ref "LED5") (pin "4") (pinfunction "BLU_4") (pintype "bidirectional"))
      (node (ref "LED6") (pin "4") (pinfunction "BLU_4") (pintype "bidirectional"))
      (node (ref "LED7") (pin "4") (pinfunction "BLU_4") (pintype "bidirectional"))
      (node (ref "LED8") (pin "4") (pinfunction "BLU_4") (pintype "bidirectional"))
    )
    (net (code "49") (name "Net-(OFFSET-3)") (class "Default")
      (node (ref "OFFSET") (pin "1") (pinfunction "3_1") (pintype "passive"))
      (node (ref "S1") (pin "5") (pinfunction "5_5") (pintype "bidirectional"))
    )
    (net (code "50") (name "Net-(PT1-3)") (class "Default")
      (node (ref "PT1") (pin "1") (pinfunction "3_1") (pintype "passive"))
      (node (ref "R3_A") (pin "2") (pinfunction "2_2") (pintype "passive"))
      (node (ref "VR3") (pin "2") (pinfunction "S_2") (pintype "passive"))
    )
    (net (code "51") (name "Net-(PT2-3)") (class "Default")
      (node (ref "PT2") (pin "1") (pinfunction "3_1") (pintype "passive"))
      (node (ref "R2_A") (pin "2") (pinfunction "2_2") (pintype "passive"))
      (node (ref "VR2") (pin "2") (pinfunction "S_2") (pintype "passive"))
    )
    (net (code "52") (name "Net-(PT3-3)") (class "Default")
      (node (ref "PT3") (pin "1") (pinfunction "3_1") (pintype "passive"))
      (node (ref "R1_A") (pin "2") (pinfunction "2_2") (pintype "passive"))
      (node (ref "VR1") (pin "2") (pinfunction "S_2") (pintype "passive"))
    )
    (net (code "53") (name "Net-(PT4-3)") (class "Default")
      (node (ref "PT4") (pin "1") (pinfunction "3_1") (pintype "passive"))
      (node (ref "R4_A") (pin "2") (pinfunction "2_2") (pintype "passive"))
      (node (ref "VR4") (pin "2") (pinfunction "S_2") (pintype "passive"))
    )
    (net (code "54") (name "Net-(TRIG_OUT-2)") (class "Default")
      (node (ref "R56") (pin "1") (pinfunction "1_1") (pintype "passive"))
      (node (ref "TRIG_OUT") (pin "P$1") (pinfunction "2_P$1") (pintype "passive"))
    )
    (net (code "55") (name "Net-(U1A-Y)") (class "Default")
      (node (ref "R56") (pin "2") (pinfunction "2_2") (pintype "passive"))
      (node (ref "U1") (pin "4") (pinfunction "Y_4") (pintype "tri_state"))
    )
    (net (code "56") (name "Net-(VR1-A)") (class "Default")
      (node (ref "R5_B") (pin "1") (pinfunction "1_1") (pintype "passive"))
      (node (ref "R6_A") (pin "1") (pinfunction "1_1") (pintype "passive"))
      (node (ref "VR1") (pin "1") (pinfunction "A_1") (pintype "passive"))
      (node (ref "VR2") (pin "1") (pinfunction "A_1") (pintype "passive"))
      (node (ref "VR3") (pin "1") (pinfunction "A_1") (pintype "passive"))
      (node (ref "VR4") (pin "1") (pinfunction "A_1") (pintype "passive"))
    )
    (net (code "57") (name "unconnected-(0_RX-3-Pad1)") (class "Default")
      (node (ref "0_RX") (pin "1") (pinfunction "3_1") (pintype "passive"))
    )
    (net (code "58") (name "unconnected-(1_TX-3-Pad1)") (class "Default")
      (node (ref "1_TX") (pin "1") (pinfunction "3_1") (pintype "passive"))
    )
    (net (code "59") (name "unconnected-(28-3-Pad1)") (class "Default")
      (node (ref "28") (pin "1") (pinfunction "3_1") (pintype "passive"))
    )
    (net (code "60") (name "unconnected-(29-3-Pad1)") (class "Default")
      (node (ref "29") (pin "1") (pinfunction "3_1") (pintype "passive"))
    )
    (net (code "61") (name "unconnected-(30-3-Pad1)") (class "Default")
      (node (ref "30") (pin "1") (pinfunction "3_1") (pintype "passive"))
    )
    (net (code "62") (name "unconnected-(31-3-Pad1)") (class "Default")
      (node (ref "31") (pin "1") (pinfunction "3_1") (pintype "passive"))
    )
    (net (code "63") (name "unconnected-(32-3-Pad1)") (class "Default")
      (node (ref "32") (pin "1") (pinfunction "3_1") (pintype "passive"))
    )
    (net (code "64") (name "unconnected-(33-3-Pad1)") (class "Default")
      (node (ref "33") (pin "1") (pinfunction "3_1") (pintype "passive"))
    )
    (net (code "65") (name "unconnected-(34-3-Pad1)") (class "Default")
      (node (ref "34") (pin "1") (pinfunction "3_1") (pintype "passive"))
    )
    (net (code "66") (name "unconnected-(35-3-Pad1)") (class "Default")
      (node (ref "35") (pin "1") (pinfunction "3_1") (pintype "passive"))
    )
    (net (code "67") (name "unconnected-(36-3-Pad1)") (class "Default")
      (node (ref "36") (pin "1") (pinfunction "3_1") (pintype "passive"))
    )
    (net (code "68") (name "unconnected-(37-3-Pad1)") (class "Default")
      (node (ref "37") (pin "1") (pinfunction "3_1") (pintype "passive"))
    )
    (net (code "69") (name "unconnected-(38-3-Pad1)") (class "Default")
      (node (ref "38") (pin "1") (pinfunction "3_1") (pintype "passive"))
    )
    (net (code "70") (name "unconnected-(39-3-Pad1)") (class "Default")
      (node (ref "39") (pin "1") (pinfunction "3_1") (pintype "passive"))
    )
    (net (code "71") (name "unconnected-(40-3-Pad1)") (class "Default")
      (node (ref "40") (pin "1") (pinfunction "3_1") (pintype "passive"))
    )
    (net (code "72") (name "unconnected-(41-3-Pad1)") (class "Default")
      (node (ref "41") (pin "1") (pinfunction "3_1") (pintype "passive"))
    )
    (net (code "73") (name "unconnected-(CV1_-3-Pad1)") (class "Default")
      (node (ref "CV1_") (pin "1") (pinfunction "3_1") (pintype "passive"))
    )
    (net (code "74") (name "unconnected-(CV6_-3-Pad1)") (class "Default")
      (node (ref "CV6_") (pin "1") (pinfunction "3_1") (pintype "passive"))
    )
    (net (code "75") (name "unconnected-(CV7-3-Pad1)") (class "Default")
      (node (ref "CV7") (pin "1") (pinfunction "3_1") (pintype "passive"))
    )
    (net (code "76") (name "unconnected-(CV7_-3-Pad1)") (class "Default")
      (node (ref "CV7_") (pin "1") (pinfunction "3_1") (pintype "passive"))
    )
    (net (code "77") (name "unconnected-(CV8-3-Pad1)") (class "Default")
      (node (ref "CV8") (pin "1") (pinfunction "3_1") (pintype "passive"))
    )
    (net (code "78") (name "unconnected-(CV8_-3-Pad1)") (class "Default")
      (node (ref "CV8_") (pin "1") (pinfunction "3_1") (pintype "passive"))
    )
    (net (code "79") (name "unconnected-(IC1-INTB-Pad9)") (class "Default")
      (node (ref "IC1") (pin "9") (pinfunction "INTB_9") (pintype "input"))
    )
    (net (code "80") (name "unconnected-(IC1-SW6-Pad19)") (class "Default")
      (node (ref "IC1") (pin "19") (pinfunction "SW6_19") (pintype "output"))
    )
    (net (code "81") (name "unconnected-(IC1-SYNC-Pad5)") (class "Default")
      (node (ref "IC1") (pin "5") (pinfunction "SYNC_5") (pintype "input"))
    )
    (net (code "82") (name "unconnected-(IO1-3-Pad1)") (class "Default")
      (node (ref "IO1") (pin "1") (pinfunction "3_1") (pintype "passive"))
    )
    (net (code "83") (name "unconnected-(IO2-3-Pad1)") (class "Default")
      (node (ref "IO2") (pin "1") (pinfunction "3_1") (pintype "passive"))
    )
    (net (code "84") (name "unconnected-(IO3-3-Pad1)") (class "Default")
      (node (ref "IO3") (pin "1") (pinfunction "3_1") (pintype "passive"))
    )
    (net (code "85") (name "unconnected-(IO4-3-Pad1)") (class "Default")
      (node (ref "IO4") (pin "1") (pinfunction "3_1") (pintype "passive"))
    )
    (net (code "86") (name "unconnected-(IO5-3-Pad1)") (class "Default")
      (node (ref "IO5") (pin "1") (pinfunction "3_1") (pintype "passive"))
    )
    (net (code "87") (name "unconnected-(IO6-3-Pad1)") (class "Default")
      (node (ref "IO6") (pin "1") (pinfunction "3_1") (pintype "passive"))
    )
    (net (code "88") (name "unconnected-(IO7-3-Pad1)") (class "Default")
      (node (ref "IO7") (pin "1") (pinfunction "3_1") (pintype "passive"))
    )
    (net (code "89") (name "unconnected-(IO8-3-Pad1)") (class "Default")
      (node (ref "IO8") (pin "1") (pinfunction "3_1") (pintype "passive"))
    )
    (net (code "90") (name "unconnected-(IO9-3-Pad1)") (class "Default")
      (node (ref "IO9") (pin "1") (pinfunction "3_1") (pintype "passive"))
    )
    (net (code "91") (name "unconnected-(IO10-3-Pad1)") (class "Default")
      (node (ref "IO10") (pin "1") (pinfunction "3_1") (pintype "passive"))
    )
    (net (code "92") (name "unconnected-(IO16-3-Pad1)") (class "Default")
      (node (ref "IO16") (pin "1") (pinfunction "3_1") (pintype "passive"))
    )
    (net (code "93") (name "unconnected-(OU1-3-PadP$2)") (class "Default")
      (node (ref "OU1") (pin "P$2") (pinfunction "3_P$2") (pintype "passive"))
    )
    (net (code "94") (name "unconnected-(OUT2-3-PadP$2)") (class "Default")
      (node (ref "OUT2") (pin "P$2") (pinfunction "3_P$2") (pintype "passive"))
    )
    (net (code "95") (name "unconnected-(OUT3-3-PadP$2)") (class "Default")
      (node (ref "OUT3") (pin "P$2") (pinfunction "3_P$2") (pintype "passive"))
    )
    (net (code "96") (name "unconnected-(OUT4-3-PadP$2)") (class "Default")
      (node (ref "OUT4") (pin "P$2") (pinfunction "3_P$2") (pintype "passive"))
    )
    (net (code "97") (name "unconnected-(OUT5-3-PadP$2)") (class "Default")
      (node (ref "OUT5") (pin "P$2") (pinfunction "3_P$2") (pintype "passive"))
    )
    (net (code "98") (name "unconnected-(OUT6-3-PadP$2)") (class "Default")
      (node (ref "OUT6") (pin "P$2") (pinfunction "3_P$2") (pintype "passive"))
    )
    (net (code "99") (name "unconnected-(OUT7-3-PadP$2)") (class "Default")
      (node (ref "OUT7") (pin "P$2") (pinfunction "3_P$2") (pintype "passive"))
    )
    (net (code "100") (name "unconnected-(OUT8-3-PadP$2)") (class "Default")
      (node (ref "OUT8") (pin "P$2") (pinfunction "3_P$2") (pintype "passive"))
    )
    (net (code "101") (name "unconnected-(PT5-3-Pad1)") (class "Default")
      (node (ref "PT5") (pin "1") (pinfunction "3_1") (pintype "passive"))
    )
    (net (code "102") (name "unconnected-(PT6-3-Pad1)") (class "Default")
      (node (ref "PT6") (pin "1") (pinfunction "3_1") (pintype "passive"))
    )
    (net (code "103") (name "unconnected-(PT7-3-Pad1)") (class "Default")
      (node (ref "PT7") (pin "1") (pinfunction "3_1") (pintype "passive"))
    )
    (net (code "104") (name "unconnected-(PT8-3-Pad1)") (class "Default")
      (node (ref "PT8") (pin "1") (pinfunction "3_1") (pintype "passive"))
    )
    (net (code "105") (name "unconnected-(S1-Pad1)") (class "Default")
      (node (ref "S1") (pin "1") (pinfunction "1_1") (pintype "bidirectional"))
    )
    (net (code "106") (name "unconnected-(TRIG_OUT-3-PadP$2)") (class "Default")
      (node (ref "TRIG_OUT") (pin "P$2") (pinfunction "3_P$2") (pintype "passive"))
    )
  )
)
